# Motorcontroller.net
KiCad netlist of a schematic drawn in EAGLE
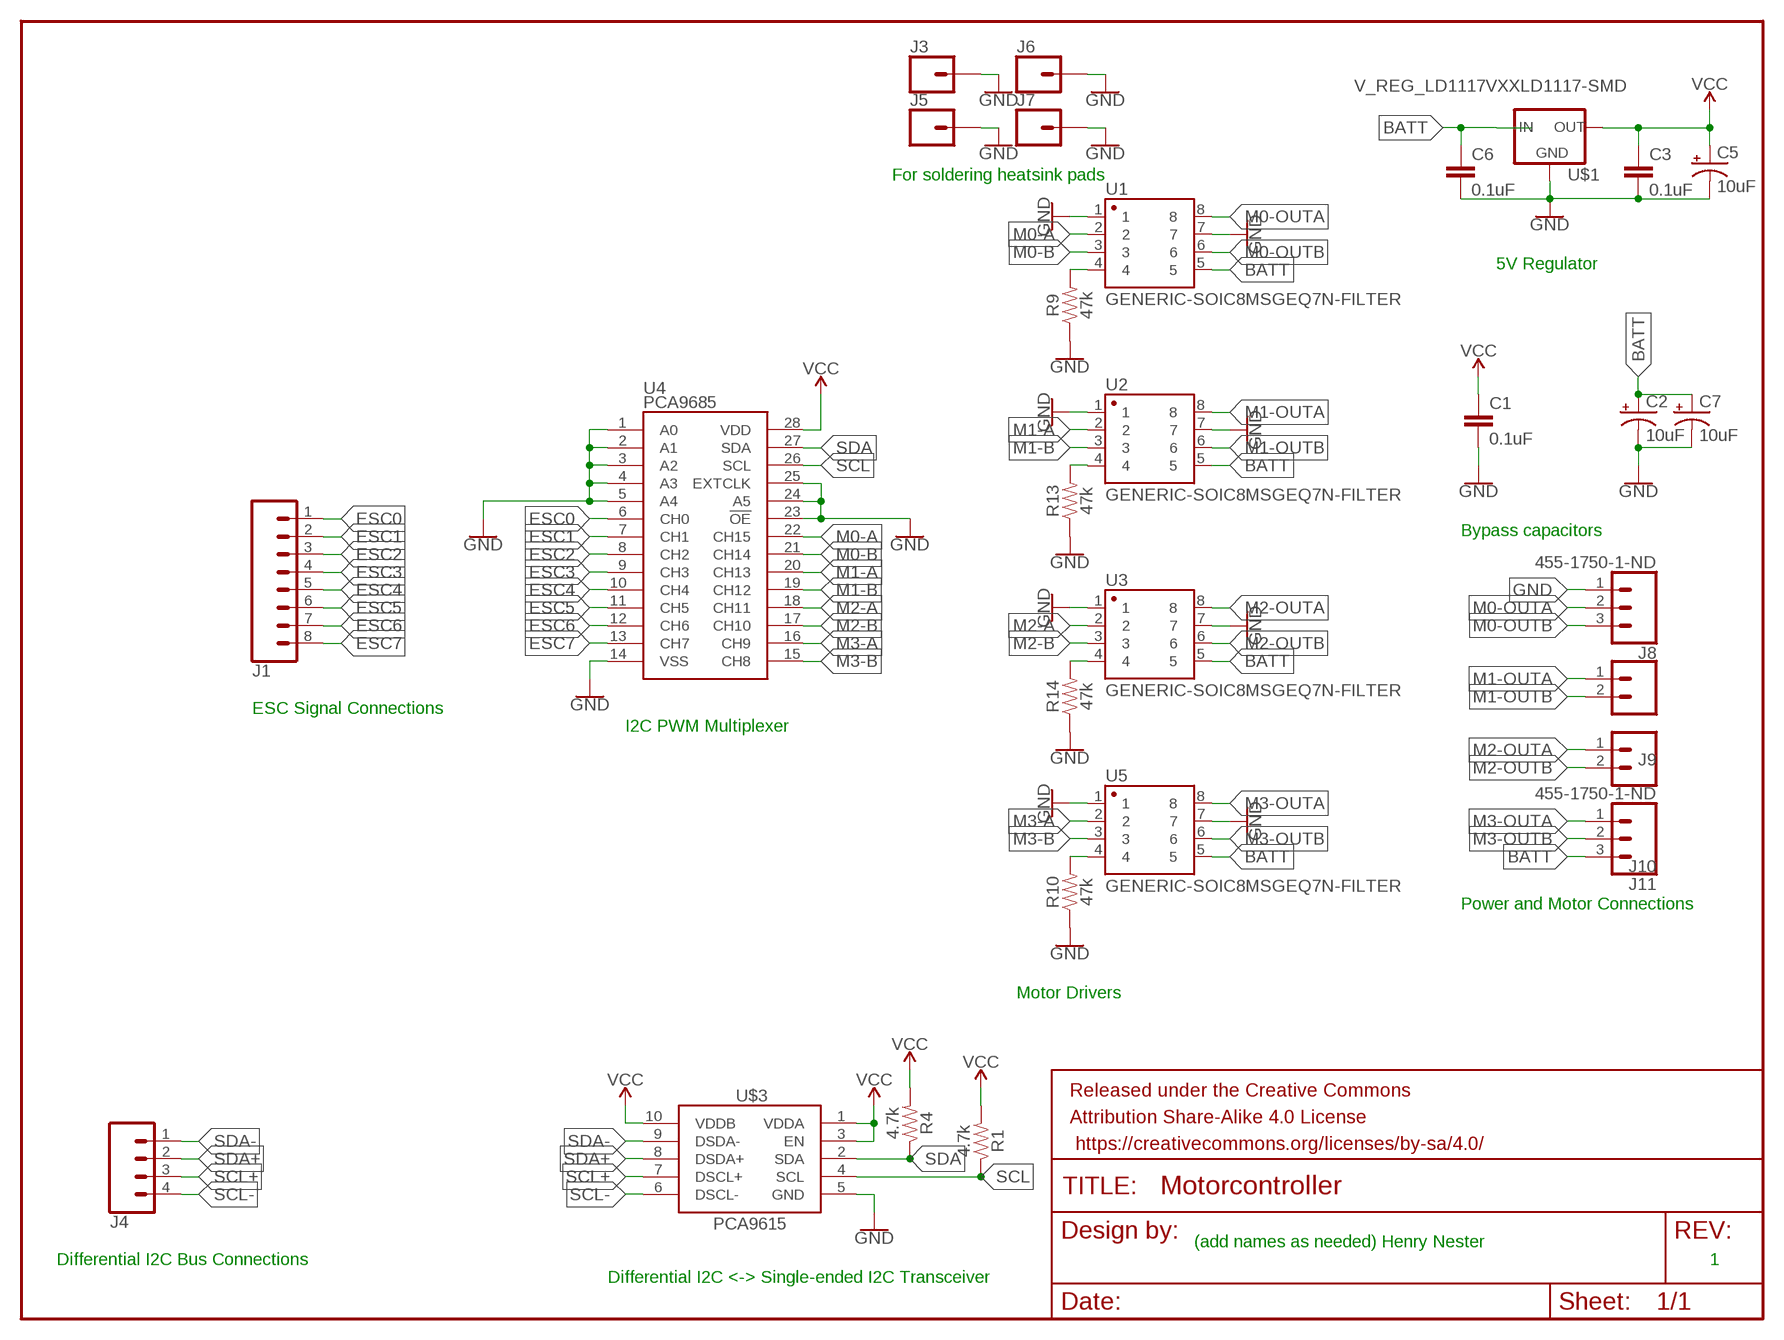
[diagram p0: schematic, sheet 1]

(export (version "E")
  (design (tool "Eeschema 10.0.6"))
  (components
    (comp (ref "C1")
      (value "0.1uF")
      (footprint "eagle-import:0603")
      (libsource (lib "eagle-import") (part "0.1UF-0603-25V-(+80/-20%)"))
    )
    (comp (ref "C2")
      (value "10uF")
      (footprint "eagle-import:CPOL-RADIAL-2.5MM-5MM")
      (libsource (lib "eagle-import") (part "10UF-POLAR-RADIAL-2.5MM-25V-20%"))
    )
    (comp (ref "C3")
      (value "0.1uF")
      (footprint "eagle-import:0603")
      (libsource (lib "eagle-import") (part "0.1UF-0603-25V-(+80/-20%)"))
    )
    (comp (ref "C5")
      (value "10uF")
      (footprint "eagle-import:CPOL-RADIAL-2.5MM-5MM")
      (libsource (lib "eagle-import") (part "10UF-POLAR-RADIAL-2.5MM-25V-20%"))
    )
    (comp (ref "C6")
      (value "0.1uF")
      (footprint "eagle-import:0603")
      (libsource (lib "eagle-import") (part "0.1UF-0603-25V-(+80/-20%)"))
    )
    (comp (ref "C7")
      (value "10uF")
      (footprint "eagle-import:CPOL-RADIAL-2.5MM-5MM")
      (libsource (lib "eagle-import") (part "10UF-POLAR-RADIAL-2.5MM-25V-20%"))
    )
    (comp (ref "FRAME1")
      (value "FRAME-LETTERNO_PACKAGE")
      (footprint "eagle-import:DUMMY")
      (fields (field (name "DESIGNER") "Nobody"))
      (libsource (lib "eagle-import") (part "FRAME-LETTERNO_PACKAGE"))
    )
    (comp (ref "J1")
      (value "CONN_08\"")
      (footprint "eagle-import:1X08")
      (libsource (lib "eagle-import") (part "CONN_08{dblquote}"))
    )
    (comp (ref "J3")
      (value "CONN_01PTH_NO_SILK_YES_STOP")
      (footprint "eagle-import:1X01_NO_SILK")
      (libsource (lib "eagle-import") (part "CONN_01PTH_NO_SILK_YES_STOP"))
    )
    (comp (ref "J4")
      (value "CONN_04")
      (footprint "eagle-import:1X04")
      (libsource (lib "eagle-import") (part "CONN_04"))
    )
    (comp (ref "J5")
      (value "CONN_01PTH_NO_SILK_YES_STOP")
      (footprint "eagle-import:1X01_NO_SILK")
      (libsource (lib "eagle-import") (part "CONN_01PTH_NO_SILK_YES_STOP"))
    )
    (comp (ref "J6")
      (value "CONN_01PTH_NO_SILK_YES_STOP")
      (footprint "eagle-import:1X01_NO_SILK")
      (libsource (lib "eagle-import") (part "CONN_01PTH_NO_SILK_YES_STOP"))
    )
    (comp (ref "J7")
      (value "CONN_01PTH_NO_SILK_YES_STOP")
      (footprint "eagle-import:1X01_NO_SILK")
      (libsource (lib "eagle-import") (part "CONN_01PTH_NO_SILK_YES_STOP"))
    )
    (comp (ref "J8")
      (value "455-1750-1-ND")
      (footprint "eagle-import:1X03")
      (libsource (lib "eagle-import") (part "CONN_03"))
    )
    (comp (ref "J9")
      (value "CONN_02")
      (footprint "eagle-import:1X02")
      (libsource (lib "eagle-import") (part "CONN_02"))
    )
    (comp (ref "J10")
      (value "CONN_02")
      (footprint "eagle-import:1X02")
      (libsource (lib "eagle-import") (part "CONN_02"))
    )
    (comp (ref "J11")
      (value "455-1750-1-ND")
      (footprint "eagle-import:1X03")
      (libsource (lib "eagle-import") (part "CONN_03"))
    )
    (comp (ref "R1")
      (value "4.7k")
      (footprint "eagle-import:0603")
      (libsource (lib "eagle-import") (part "4.7KOHM-0603-1/10W-1%"))
    )
    (comp (ref "R4")
      (value "4.7k")
      (footprint "eagle-import:0603")
      (libsource (lib "eagle-import") (part "4.7KOHM-0603-1/10W-1%"))
    )
    (comp (ref "R9")
      (value "47k")
      (footprint "eagle-import:0603")
      (libsource (lib "eagle-import") (part "47KOHM-0603-1/10W-1%"))
    )
    (comp (ref "R10")
      (value "47k")
      (footprint "eagle-import:0603")
      (libsource (lib "eagle-import") (part "47KOHM-0603-1/10W-1%"))
    )
    (comp (ref "R13")
      (value "47k")
      (footprint "eagle-import:0603")
      (libsource (lib "eagle-import") (part "47KOHM-0603-1/10W-1%"))
    )
    (comp (ref "R14")
      (value "47k")
      (footprint "eagle-import:0603")
      (libsource (lib "eagle-import") (part "47KOHM-0603-1/10W-1%"))
    )
    (comp (ref "U$1")
      (value "V_REG_LD1117VXXLD1117-SMD")
      (footprint "eagle-import:SOT223")
      (libsource (lib "eagle-import") (part "V_REG_LD1117VXXLD1117-SMD"))
    )
    (comp (ref "U$3")
      (value "PCA9615")
      (footprint "eagle-import:TSSOP10")
      (libsource (lib "eagle-import") (part "PCA9615"))
    )
    (comp (ref "U1")
      (value "GENERIC-SOIC8MSGEQ7N-FILTER")
      (footprint "eagle-import:SO08")
      (libsource (lib "eagle-import") (part "GENERIC-SOIC8MSGEQ7N-FILTER"))
    )
    (comp (ref "U2")
      (value "GENERIC-SOIC8MSGEQ7N-FILTER")
      (footprint "eagle-import:SO08")
      (libsource (lib "eagle-import") (part "GENERIC-SOIC8MSGEQ7N-FILTER"))
    )
    (comp (ref "U3")
      (value "GENERIC-SOIC8MSGEQ7N-FILTER")
      (footprint "eagle-import:SO08")
      (libsource (lib "eagle-import") (part "GENERIC-SOIC8MSGEQ7N-FILTER"))
    )
    (comp (ref "U4")
      (value "PCA9685")
      (footprint "eagle-import:TSSOP-28_4MM")
      (libsource (lib "eagle-import") (part "PCA9685"))
    )
    (comp (ref "U5")
      (value "GENERIC-SOIC8MSGEQ7N-FILTER")
      (footprint "eagle-import:SO08")
      (libsource (lib "eagle-import") (part "GENERIC-SOIC8MSGEQ7N-FILTER"))
    )
  )
  (nets
    (net (code "1") (name "BATT") (class "Default")
      (node (ref "C2") (pin "1") (pinfunction "+_1") (pintype "passive"))
      (node (ref "C6") (pin "1") (pinfunction "1_1") (pintype "passive"))
      (node (ref "C7") (pin "1") (pinfunction "+_1") (pintype "passive"))
      (node (ref "J11") (pin "3") (pinfunction "3_3") (pintype "passive"))
      (node (ref "U$1") (pin "3") (pinfunction "IN_3") (pintype "input"))
      (node (ref "U1") (pin "5") (pinfunction "5_5") (pintype "bidirectional"))
      (node (ref "U2") (pin "5") (pinfunction "5_5") (pintype "bidirectional"))
      (node (ref "U3") (pin "5") (pinfunction "5_5") (pintype "bidirectional"))
      (node (ref "U5") (pin "5") (pinfunction "5_5") (pintype "bidirectional"))
    )
    (net (code "2") (name "ESC0") (class "Default")
      (node (ref "J1") (pin "1") (pinfunction "1_1") (pintype "passive"))
      (node (ref "U4") (pin "6") (pinfunction "CH0_6") (pintype "bidirectional"))
    )
    (net (code "3") (name "ESC1") (class "Default")
      (node (ref "J1") (pin "2") (pinfunction "2_2") (pintype "passive"))
      (node (ref "U4") (pin "7") (pinfunction "CH1_7") (pintype "bidirectional"))
    )
    (net (code "4") (name "ESC2") (class "Default")
      (node (ref "J1") (pin "3") (pinfunction "3_3") (pintype "passive"))
      (node (ref "U4") (pin "8") (pinfunction "CH2_8") (pintype "bidirectional"))
    )
    (net (code "5") (name "ESC3") (class "Default")
      (node (ref "J1") (pin "4") (pinfunction "4_4") (pintype "passive"))
      (node (ref "U4") (pin "9") (pinfunction "CH3_9") (pintype "bidirectional"))
    )
    (net (code "6") (name "ESC4") (class "Default")
      (node (ref "J1") (pin "5") (pinfunction "5_5") (pintype "passive"))
      (node (ref "U4") (pin "10") (pinfunction "CH4_10") (pintype "bidirectional"))
    )
    (net (code "7") (name "ESC5") (class "Default")
      (node (ref "J1") (pin "6") (pinfunction "6_6") (pintype "passive"))
      (node (ref "U4") (pin "11") (pinfunction "CH5_11") (pintype "bidirectional"))
    )
    (net (code "8") (name "ESC6") (class "Default")
      (node (ref "J1") (pin "7") (pinfunction "7_7") (pintype "passive"))
      (node (ref "U4") (pin "12") (pinfunction "CH6_12") (pintype "bidirectional"))
    )
    (net (code "9") (name "ESC7") (class "Default")
      (node (ref "J1") (pin "8") (pinfunction "8_8") (pintype "passive"))
      (node (ref "U4") (pin "13") (pinfunction "CH7_13") (pintype "bidirectional"))
    )
    (net (code "10") (name "GND") (class "Default")
      (node (ref "C1") (pin "2") (pinfunction "2_2") (pintype "passive"))
      (node (ref "C2") (pin "2") (pinfunction "-_2") (pintype "passive"))
      (node (ref "C3") (pin "2") (pinfunction "2_2") (pintype "passive"))
      (node (ref "C5") (pin "2") (pinfunction "-_2") (pintype "passive"))
      (node (ref "C6") (pin "2") (pinfunction "2_2") (pintype "passive"))
      (node (ref "C7") (pin "2") (pinfunction "-_2") (pintype "passive"))
      (node (ref "J3") (pin "1") (pinfunction "1_1") (pintype "passive"))
      (node (ref "J5") (pin "1") (pinfunction "1_1") (pintype "passive"))
      (node (ref "J6") (pin "1") (pinfunction "1_1") (pintype "passive"))
      (node (ref "J7") (pin "1") (pinfunction "1_1") (pintype "passive"))
      (node (ref "J8") (pin "1") (pinfunction "1_1") (pintype "passive"))
      (node (ref "R10") (pin "1") (pinfunction "1_1") (pintype "passive"))
      (node (ref "R13") (pin "1") (pinfunction "1_1") (pintype "passive"))
      (node (ref "R14") (pin "1") (pinfunction "1_1") (pintype "passive"))
      (node (ref "R9") (pin "1") (pinfunction "1_1") (pintype "passive"))
      (node (ref "U$1") (pin "1") (pinfunction "GND_1") (pintype "input"))
      (node (ref "U$3") (pin "5") (pinfunction "GND_5") (pintype "bidirectional"))
      (node (ref "U1") (pin "1") (pinfunction "1_1") (pintype "bidirectional"))
      (node (ref "U1") (pin "7") (pinfunction "7_7") (pintype "bidirectional"))
      (node (ref "U2") (pin "1") (pinfunction "1_1") (pintype "bidirectional"))
      (node (ref "U2") (pin "7") (pinfunction "7_7") (pintype "bidirectional"))
      (node (ref "U3") (pin "1") (pinfunction "1_1") (pintype "bidirectional"))
      (node (ref "U3") (pin "7") (pinfunction "7_7") (pintype "bidirectional"))
      (node (ref "U4") (pin "1") (pinfunction "A0_1") (pintype "bidirectional"))
      (node (ref "U4") (pin "14") (pinfunction "VSS_14") (pintype "bidirectional"))
      (node (ref "U4") (pin "2") (pinfunction "A1_2") (pintype "bidirectional"))
      (node (ref "U4") (pin "23") (pinfunction "~{OE}_23") (pintype "bidirectional"))
      (node (ref "U4") (pin "24") (pinfunction "A5_24") (pintype "bidirectional"))
      (node (ref "U4") (pin "25") (pinfunction "EXTCLK_25") (pintype "bidirectional"))
      (node (ref "U4") (pin "3") (pinfunction "A2_3") (pintype "bidirectional"))
      (node (ref "U4") (pin "4") (pinfunction "A3_4") (pintype "bidirectional"))
      (node (ref "U4") (pin "5") (pinfunction "A4_5") (pintype "bidirectional"))
      (node (ref "U5") (pin "1") (pinfunction "1_1") (pintype "bidirectional"))
      (node (ref "U5") (pin "7") (pinfunction "7_7") (pintype "bidirectional"))
    )
    (net (code "11") (name "M0-A") (class "Default")
      (node (ref "U1") (pin "2") (pinfunction "2_2") (pintype "bidirectional"))
      (node (ref "U4") (pin "22") (pinfunction "CH15_22") (pintype "bidirectional"))
    )
    (net (code "12") (name "M0-B") (class "Default")
      (node (ref "U1") (pin "3") (pinfunction "3_3") (pintype "bidirectional"))
      (node (ref "U4") (pin "21") (pinfunction "CH14_21") (pintype "bidirectional"))
    )
    (net (code "13") (name "M0-OUTA") (class "Default")
      (node (ref "J8") (pin "2") (pinfunction "2_2") (pintype "passive"))
      (node (ref "U1") (pin "8") (pinfunction "8_8") (pintype "bidirectional"))
    )
    (net (code "14") (name "M0-OUTB") (class "Default")
      (node (ref "J8") (pin "3") (pinfunction "3_3") (pintype "passive"))
      (node (ref "U1") (pin "6") (pinfunction "6_6") (pintype "bidirectional"))
    )
    (net (code "15") (name "M1-A") (class "Default")
      (node (ref "U2") (pin "2") (pinfunction "2_2") (pintype "bidirectional"))
      (node (ref "U4") (pin "20") (pinfunction "CH13_20") (pintype "bidirectional"))
    )
    (net (code "16") (name "M1-B") (class "Default")
      (node (ref "U2") (pin "3") (pinfunction "3_3") (pintype "bidirectional"))
      (node (ref "U4") (pin "19") (pinfunction "CH12_19") (pintype "bidirectional"))
    )
    (net (code "17") (name "M1-OUTA") (class "Default")
      (node (ref "J9") (pin "1") (pinfunction "1_1") (pintype "passive"))
      (node (ref "U2") (pin "8") (pinfunction "8_8") (pintype "bidirectional"))
    )
    (net (code "18") (name "M1-OUTB") (class "Default")
      (node (ref "J9") (pin "2") (pinfunction "2_2") (pintype "passive"))
      (node (ref "U2") (pin "6") (pinfunction "6_6") (pintype "bidirectional"))
    )
    (net (code "19") (name "M2-A") (class "Default")
      (node (ref "U3") (pin "2") (pinfunction "2_2") (pintype "bidirectional"))
      (node (ref "U4") (pin "18") (pinfunction "CH11_18") (pintype "bidirectional"))
    )
    (net (code "20") (name "M2-B") (class "Default")
      (node (ref "U3") (pin "3") (pinfunction "3_3") (pintype "bidirectional"))
      (node (ref "U4") (pin "17") (pinfunction "CH10_17") (pintype "bidirectional"))
    )
    (net (code "21") (name "M2-OUTA") (class "Default")
      (node (ref "J10") (pin "1") (pinfunction "1_1") (pintype "passive"))
      (node (ref "U3") (pin "8") (pinfunction "8_8") (pintype "bidirectional"))
    )
    (net (code "22") (name "M2-OUTB") (class "Default")
      (node (ref "J10") (pin "2") (pinfunction "2_2") (pintype "passive"))
      (node (ref "U3") (pin "6") (pinfunction "6_6") (pintype "bidirectional"))
    )
    (net (code "23") (name "M3-A") (class "Default")
      (node (ref "U4") (pin "16") (pinfunction "CH9_16") (pintype "bidirectional"))
      (node (ref "U5") (pin "2") (pinfunction "2_2") (pintype "bidirectional"))
    )
    (net (code "24") (name "M3-B") (class "Default")
      (node (ref "U4") (pin "15") (pinfunction "CH8_15") (pintype "bidirectional"))
      (node (ref "U5") (pin "3") (pinfunction "3_3") (pintype "bidirectional"))
    )
    (net (code "25") (name "M3-OUTA") (class "Default")
      (node (ref "J11") (pin "1") (pinfunction "1_1") (pintype "passive"))
      (node (ref "U5") (pin "8") (pinfunction "8_8") (pintype "bidirectional"))
    )
    (net (code "26") (name "M3-OUTB") (class "Default")
      (node (ref "J11") (pin "2") (pinfunction "2_2") (pintype "passive"))
      (node (ref "U5") (pin "6") (pinfunction "6_6") (pintype "bidirectional"))
    )
    (net (code "27") (name "Net-(R9-Pad2)") (class "Default")
      (node (ref "R9") (pin "2") (pinfunction "2_2") (pintype "passive"))
      (node (ref "U1") (pin "4") (pinfunction "4_4") (pintype "bidirectional"))
    )
    (net (code "28") (name "Net-(R10-Pad2)") (class "Default")
      (node (ref "R10") (pin "2") (pinfunction "2_2") (pintype "passive"))
      (node (ref "U5") (pin "4") (pinfunction "4_4") (pintype "bidirectional"))
    )
    (net (code "29") (name "Net-(R13-Pad2)") (class "Default")
      (node (ref "R13") (pin "2") (pinfunction "2_2") (pintype "passive"))
      (node (ref "U2") (pin "4") (pinfunction "4_4") (pintype "bidirectional"))
    )
    (net (code "30") (name "Net-(R14-Pad2)") (class "Default")
      (node (ref "R14") (pin "2") (pinfunction "2_2") (pintype "passive"))
      (node (ref "U3") (pin "4") (pinfunction "4_4") (pintype "bidirectional"))
    )
    (net (code "31") (name "SCL") (class "Default")
      (node (ref "R1") (pin "1") (pinfunction "1_1") (pintype "passive"))
      (node (ref "U$3") (pin "4") (pinfunction "SCL_4") (pintype "bidirectional"))
      (node (ref "U4") (pin "26") (pinfunction "SCL_26") (pintype "bidirectional"))
    )
    (net (code "32") (name "SCL+") (class "Default")
      (node (ref "J4") (pin "3") (pinfunction "3_3") (pintype "passive"))
      (node (ref "U$3") (pin "7") (pinfunction "DSCL+_7") (pintype "bidirectional"))
    )
    (net (code "33") (name "SCL-") (class "Default")
      (node (ref "J4") (pin "4") (pinfunction "4_4") (pintype "passive"))
      (node (ref "U$3") (pin "6") (pinfunction "DSCL-_6") (pintype "bidirectional"))
    )
    (net (code "34") (name "SDA") (class "Default")
      (node (ref "R4") (pin "1") (pinfunction "1_1") (pintype "passive"))
      (node (ref "U$3") (pin "2") (pinfunction "SDA_2") (pintype "bidirectional"))
      (node (ref "U4") (pin "27") (pinfunction "SDA_27") (pintype "bidirectional"))
    )
    (net (code "35") (name "SDA+") (class "Default")
      (node (ref "J4") (pin "2") (pinfunction "2_2") (pintype "passive"))
      (node (ref "U$3") (pin "8") (pinfunction "DSDA+_8") (pintype "bidirectional"))
    )
    (net (code "36") (name "SDA-") (class "Default")
      (node (ref "J4") (pin "1") (pinfunction "1_1") (pintype "passive"))
      (node (ref "U$3") (pin "9") (pinfunction "DSDA-_9") (pintype "bidirectional"))
    )
    (net (code "37") (name "VCC") (class "Default")
      (node (ref "C1") (pin "1") (pinfunction "1_1") (pintype "passive"))
      (node (ref "C3") (pin "1") (pinfunction "1_1") (pintype "passive"))
      (node (ref "C5") (pin "1") (pinfunction "+_1") (pintype "passive"))
      (node (ref "R1") (pin "2") (pinfunction "2_2") (pintype "passive"))
      (node (ref "R4") (pin "2") (pinfunction "2_2") (pintype "passive"))
      (node (ref "U$1") (pin "2") (pinfunction "OUT_2") (pintype "passive"))
      (node (ref "U$3") (pin "1") (pinfunction "VDDA_1") (pintype "bidirectional"))
      (node (ref "U$3") (pin "10") (pinfunction "VDDB_10") (pintype "bidirectional"))
      (node (ref "U$3") (pin "3") (pinfunction "EN_3") (pintype "bidirectional"))
      (node (ref "U4") (pin "28") (pinfunction "VDD_28") (pintype "bidirectional"))
    )
  )
)
